# CPU.net
KiCad netlist of a schematic drawn in Altium Designer
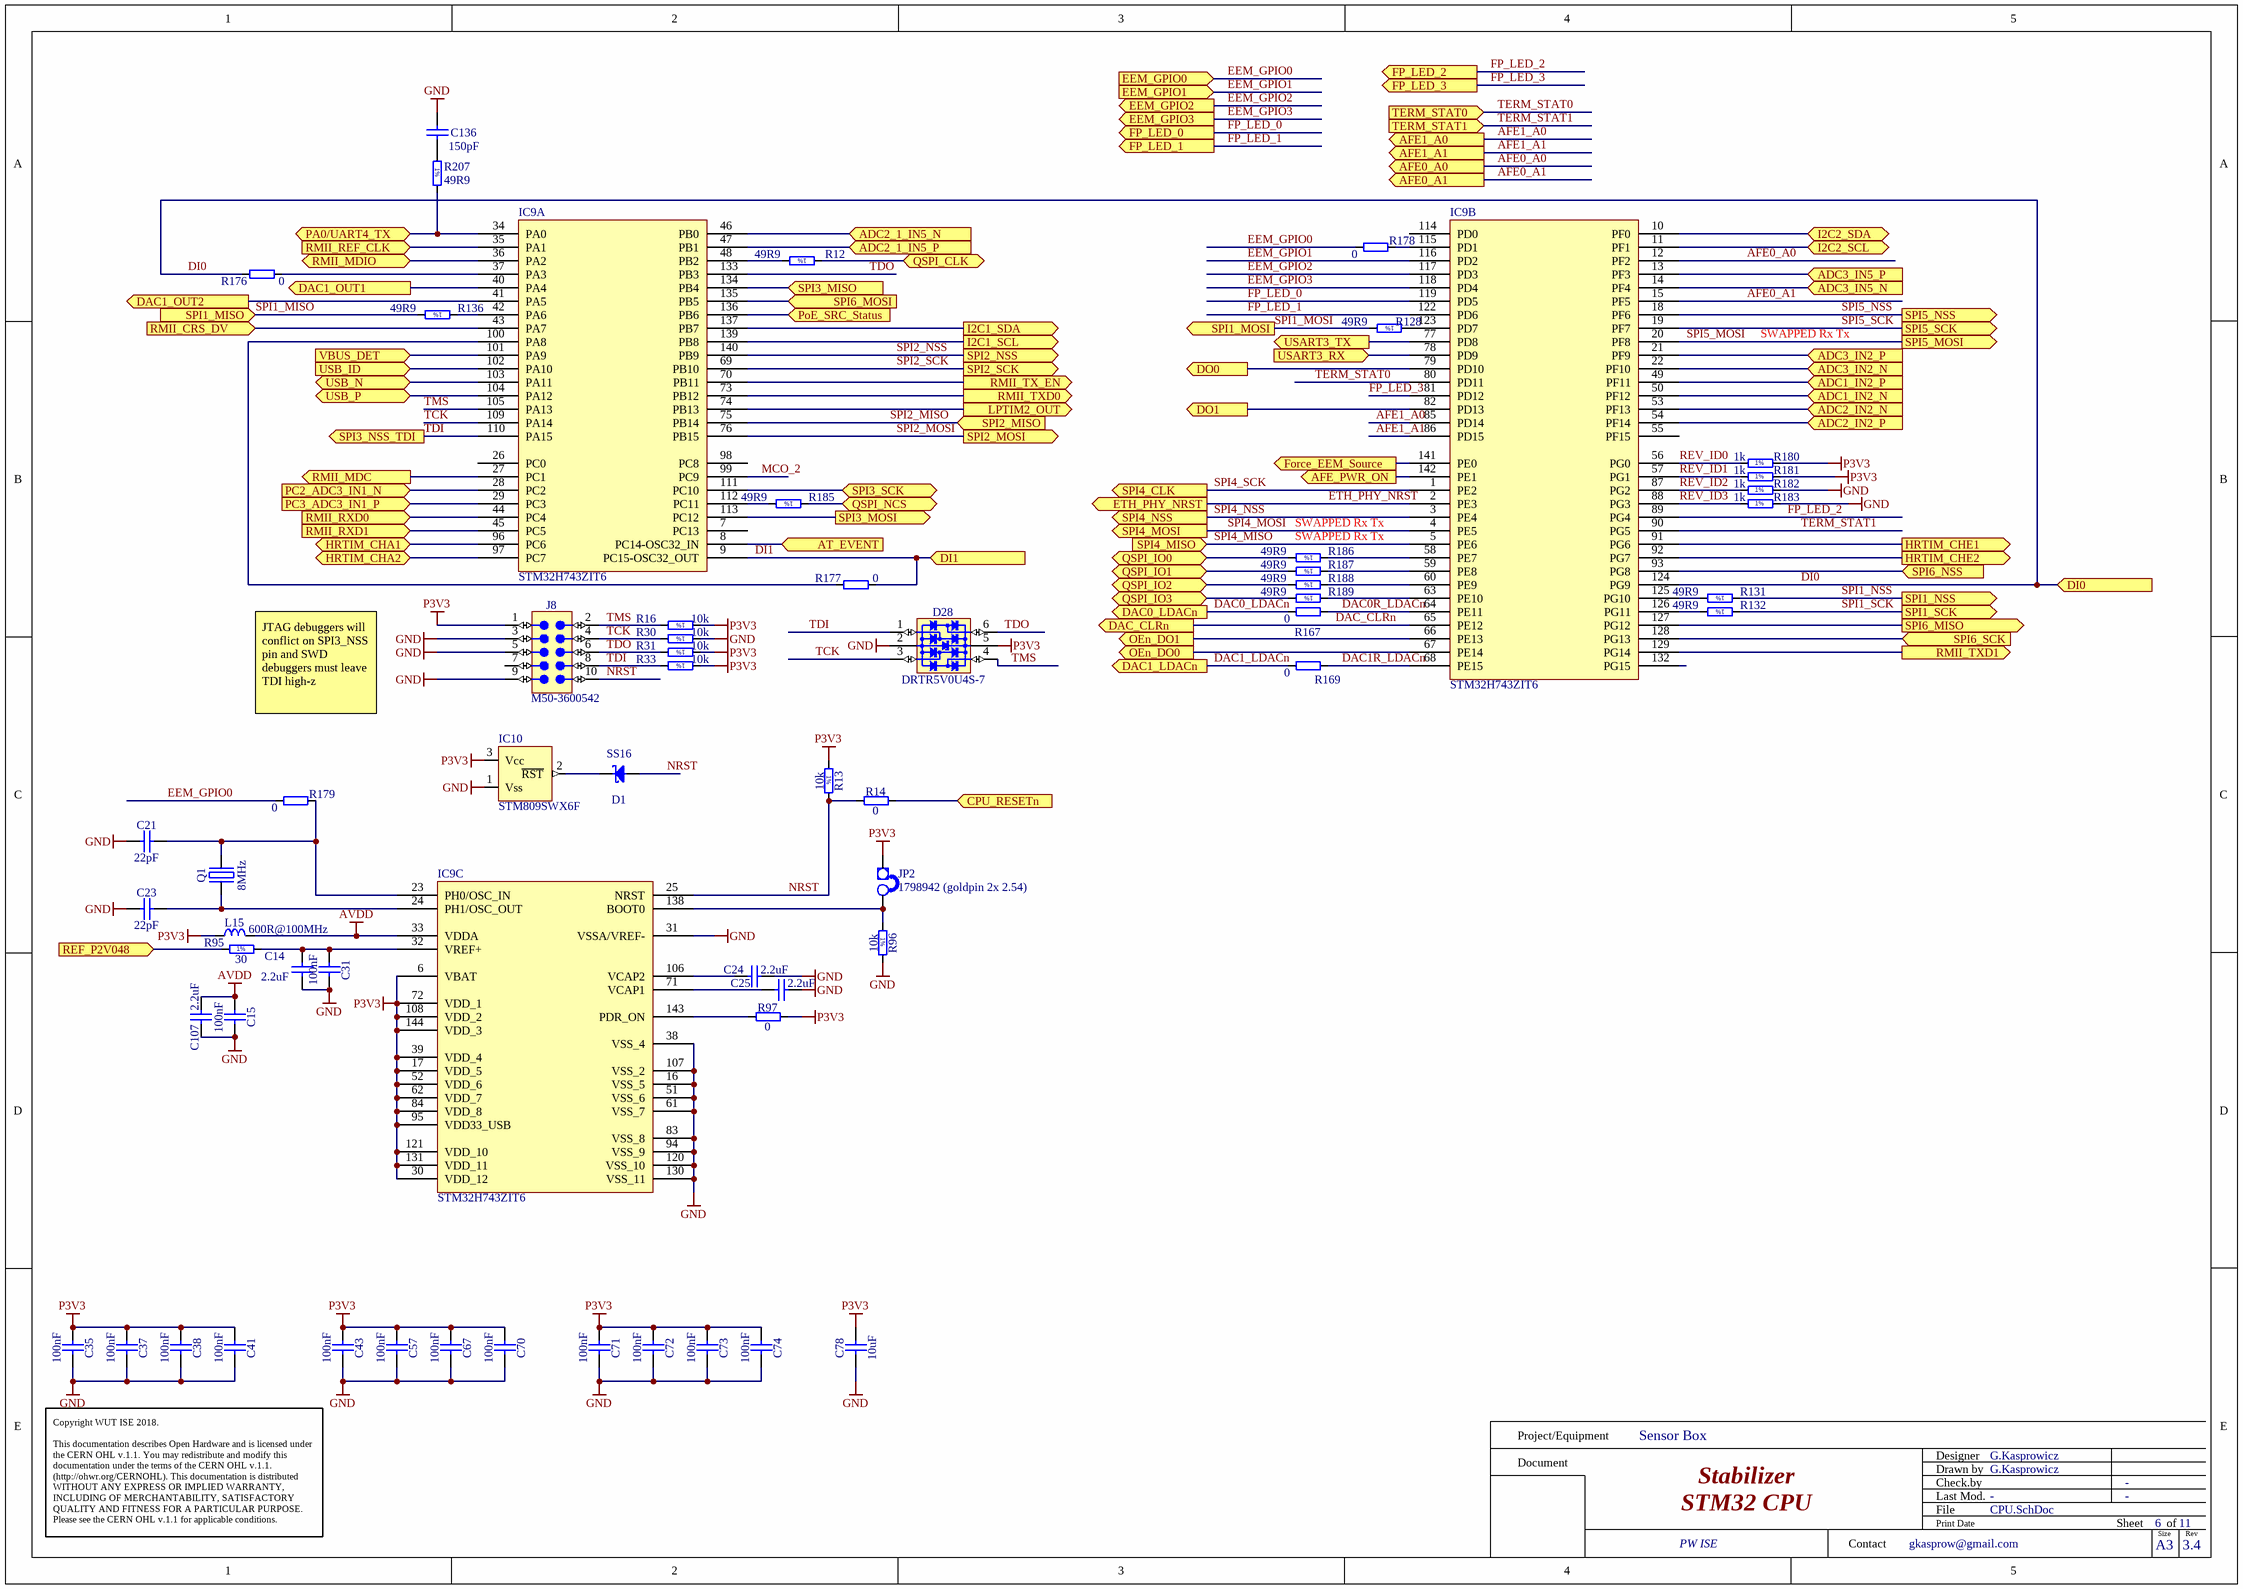
[diagram p0: CPU.SchDoc]

(export (version "E")
  (design (tool "Eeschema 10.0.6"))
  (components
    (comp (ref "C14")
      (value "2.2uF")
      (footprint "CAPC1608X90N")
      (description "Non-polarised capacitor")
      (fields
        (field (name "PART NUMBER") "CC0603_2.2UF_10V_20%_X7R")
        (field (name "VOLTAGE") "10V")
        (field (name "AUTHOR") "CERN DEM JLC")
      )
      (libsource (lib "Capacitors") (part "Capacitor - non polarized"))
    )
    (comp (ref "C15")
      (value "100nF")
      (footprint "CAPC1005X55N")
      (description "Non-polarised capacitor")
      (fields
        (field (name "PART NUMBER") "CC0402_100NF_16V_10%_X5R")
        (field (name "VOLTAGE") "16V")
        (field (name "AUTHOR") "CERN DEM JLC")
      )
      (libsource (lib "Capacitors") (part "Capacitor - non polarized"))
    )
    (comp (ref "C21")
      (value "22pF")
      (footprint "CAPC1005X55N")
      (description "Non-polarised capacitor")
      (fields
        (field (name "PART NUMBER") "CC0402_22PF_50V_5%_C0G")
        (field (name "VOLTAGE") "50V")
        (field (name "AUTHOR") "CERN DEM JLC")
      )
      (libsource (lib "Capacitors") (part "Capacitor - non polarized"))
    )
    (comp (ref "C23")
      (value "22pF")
      (footprint "CAPC1005X55N")
      (description "Non-polarised capacitor")
      (fields
        (field (name "PART NUMBER") "CC0402_22PF_50V_5%_C0G")
        (field (name "VOLTAGE") "50V")
        (field (name "AUTHOR") "CERN DEM JLC")
      )
      (libsource (lib "Capacitors") (part "Capacitor - non polarized"))
    )
    (comp (ref "C24")
      (value "2.2uF")
      (footprint "CAPC1608X90N")
      (description "Non-polarised capacitor")
      (fields
        (field (name "PART NUMBER") "CC0603_2.2UF_10V_20%_X7R")
        (field (name "VOLTAGE") "10V")
        (field (name "AUTHOR") "CERN DEM JLC")
      )
      (libsource (lib "Capacitors") (part "Capacitor - non polarized"))
    )
    (comp (ref "C25")
      (value "2.2uF")
      (footprint "CAPC1608X90N")
      (description "Non-polarised capacitor")
      (fields
        (field (name "PART NUMBER") "CC0603_2.2UF_10V_20%_X7R")
        (field (name "VOLTAGE") "10V")
        (field (name "AUTHOR") "CERN DEM JLC")
      )
      (libsource (lib "Capacitors") (part "Capacitor - non polarized"))
    )
    (comp (ref "C31")
      (value "100nF")
      (footprint "CAPC1005X55N")
      (description "Non-polarised capacitor")
      (fields
        (field (name "PART NUMBER") "CC0402_100NF_16V_10%_X5R")
        (field (name "VOLTAGE") "16V")
        (field (name "AUTHOR") "CERN DEM JLC")
      )
      (libsource (lib "Capacitors") (part "Capacitor - non polarized"))
    )
    (comp (ref "C35")
      (value "100nF")
      (footprint "CAPC1005X55N")
      (description "Non-polarised capacitor")
      (fields
        (field (name "PART NUMBER") "CC0402_100NF_16V_10%_X5R")
        (field (name "VOLTAGE") "16V")
        (field (name "AUTHOR") "CERN DEM JLC")
      )
      (libsource (lib "Capacitors") (part "Capacitor - non polarized"))
    )
    (comp (ref "C37")
      (value "100nF")
      (footprint "CAPC1005X55N")
      (description "Non-polarised capacitor")
      (fields
        (field (name "PART NUMBER") "CC0402_100NF_16V_10%_X5R")
        (field (name "VOLTAGE") "16V")
        (field (name "AUTHOR") "CERN DEM JLC")
      )
      (libsource (lib "Capacitors") (part "Capacitor - non polarized"))
    )
    (comp (ref "C38")
      (value "100nF")
      (footprint "CAPC1005X55N")
      (description "Non-polarised capacitor")
      (fields
        (field (name "PART NUMBER") "CC0402_100NF_16V_10%_X5R")
        (field (name "VOLTAGE") "16V")
        (field (name "AUTHOR") "CERN DEM JLC")
      )
      (libsource (lib "Capacitors") (part "Capacitor - non polarized"))
    )
    (comp (ref "C41")
      (value "100nF")
      (footprint "CAPC1005X55N")
      (description "Non-polarised capacitor")
      (fields
        (field (name "PART NUMBER") "CC0402_100NF_16V_10%_X5R")
        (field (name "VOLTAGE") "16V")
        (field (name "AUTHOR") "CERN DEM JLC")
      )
      (libsource (lib "Capacitors") (part "Capacitor - non polarized"))
    )
    (comp (ref "C43")
      (value "100nF")
      (footprint "CAPC1005X55N")
      (description "Non-polarised capacitor")
      (fields
        (field (name "PART NUMBER") "CC0402_100NF_16V_10%_X5R")
        (field (name "VOLTAGE") "16V")
        (field (name "AUTHOR") "CERN DEM JLC")
      )
      (libsource (lib "Capacitors") (part "Capacitor - non polarized"))
    )
    (comp (ref "C57")
      (value "100nF")
      (footprint "CAPC1005X55N")
      (description "Non-polarised capacitor")
      (fields
        (field (name "PART NUMBER") "CC0402_100NF_16V_10%_X5R")
        (field (name "VOLTAGE") "16V")
        (field (name "AUTHOR") "CERN DEM JLC")
      )
      (libsource (lib "Capacitors") (part "Capacitor - non polarized"))
    )
    (comp (ref "C67")
      (value "100nF")
      (footprint "CAPC1005X55N")
      (description "Non-polarised capacitor")
      (fields
        (field (name "PART NUMBER") "CC0402_100NF_16V_10%_X5R")
        (field (name "VOLTAGE") "16V")
        (field (name "AUTHOR") "CERN DEM JLC")
      )
      (libsource (lib "Capacitors") (part "Capacitor - non polarized"))
    )
    (comp (ref "C70")
      (value "100nF")
      (footprint "CAPC1005X55N")
      (description "Non-polarised capacitor")
      (fields
        (field (name "PART NUMBER") "CC0402_100NF_16V_10%_X5R")
        (field (name "VOLTAGE") "16V")
        (field (name "AUTHOR") "CERN DEM JLC")
      )
      (libsource (lib "Capacitors") (part "Capacitor - non polarized"))
    )
    (comp (ref "C71")
      (value "100nF")
      (footprint "CAPC1005X55N")
      (description "Non-polarised capacitor")
      (fields
        (field (name "PART NUMBER") "CC0402_100NF_16V_10%_X5R")
        (field (name "VOLTAGE") "16V")
        (field (name "AUTHOR") "CERN DEM JLC")
      )
      (libsource (lib "Capacitors") (part "Capacitor - non polarized"))
    )
    (comp (ref "C72")
      (value "100nF")
      (footprint "CAPC1005X55N")
      (description "Non-polarised capacitor")
      (fields
        (field (name "PART NUMBER") "CC0402_100NF_16V_10%_X5R")
        (field (name "VOLTAGE") "16V")
        (field (name "AUTHOR") "CERN DEM JLC")
      )
      (libsource (lib "Capacitors") (part "Capacitor - non polarized"))
    )
    (comp (ref "C73")
      (value "100nF")
      (footprint "CAPC1005X55N")
      (description "Non-polarised capacitor")
      (fields
        (field (name "PART NUMBER") "CC0402_100NF_16V_10%_X5R")
        (field (name "VOLTAGE") "16V")
        (field (name "AUTHOR") "CERN DEM JLC")
      )
      (libsource (lib "Capacitors") (part "Capacitor - non polarized"))
    )
    (comp (ref "C74")
      (value "100nF")
      (footprint "CAPC1005X55N")
      (description "Non-polarised capacitor")
      (fields
        (field (name "PART NUMBER") "CC0402_100NF_16V_10%_X5R")
        (field (name "VOLTAGE") "16V")
        (field (name "AUTHOR") "CERN DEM JLC")
      )
      (libsource (lib "Capacitors") (part "Capacitor - non polarized"))
    )
    (comp (ref "C78")
      (value "10uF")
      (footprint "CAPC2012X95N")
      (description "Non-polarised capacitor")
      (fields
        (field (name "PART NUMBER") "CC0805_10UF_25V_10%_X5R")
        (field (name "VOLTAGE") "25V")
        (field (name "AUTHOR") "CERN DEM JLC")
      )
      (libsource (lib "Capacitors") (part "Capacitor - non polarized"))
    )
    (comp (ref "C107")
      (value "2.2uF")
      (footprint "CAPC1608X90N")
      (description "Non-polarised capacitor")
      (fields
        (field (name "PART NUMBER") "CC0603_2.2UF_10V_20%_X7R")
        (field (name "VOLTAGE") "10V")
        (field (name "AUTHOR") "CERN DEM JLC")
      )
      (libsource (lib "Capacitors") (part "Capacitor - non polarized"))
    )
    (comp (ref "C136")
      (value "150pF")
      (footprint "CAPC1608X87N")
      (description "Non-polarised capacitor")
      (fields
        (field (name "PART NUMBER") "CC0603_150PF_50V_1%_NP0")
        (field (name "VOLTAGE") "50V")
        (field (name "AUTHOR") "CERN DEM MR")
      )
      (libsource (lib "Capacitors") (part "Capacitor - non polarized"))
    )
    (comp (ref "D1")
      (value "SS16")
      (footprint "DIOM5127X229N")
      (description "Schottky Diode")
      (fields
        (field (name "VOLTAGE") "60V")
        (field (name "POWER") "1A")
        (field (name "AUTHOR") "CERN DEM JLC")
      )
      (libsource (lib "ICs And Semiconductors") (part "Diode Schottky"))
    )
    (comp (ref "D28")
      (value "DRTR5V0U4S-7")
      (footprint "SOT65P210X110-6N")
      (description "Integrated Quad Ultra-Low Capacitance ESD Protection")
      (fields (field (name "MANUFACTURER") "DIODES") (field (name "AUTHOR") "GK"))
      (libsource (lib "Diodes") (part "D_TVS_DRTR5V0U4S-7"))
    )
    (comp (ref "IC9")
      (value "STM32H743ZIT6")
      (footprint "TSQFP50P2200X2200X160-144N")
      (description "32-bit Arm® Cortex-M7 400MHz MCUs, up to 2MB Flash,\r\n1MB RAM, 46 com. and analog interfaces")
      (libsource (lib "LIBRARY_SCH") (part "UPC_STM32H743ZIT6"))
    )
    (comp (ref "IC10")
      (value "STM809SWX6F")
      (footprint "SOT-23")
      (description "2.93V  Reset circuit")
      (libsource (lib "LIBRARY_SCH") (part "VMON_STM809"))
    )
    (comp (ref "J8")
      (value "Header 10")
      (footprint "HARWIN_M50-3600542")
      (description "10 Contacts - Pitch 1.27mm - Dual Row SMT Vertical Pin Header (Post Lead = 3mm, Insulator 1mm)")
      (fields
        (field (name "PART NUMBER") "HARWIN_M50-3600542")
        (field (name "MANUFACTURER") "HARWIN")
        (field (name "MANUFACTURER PART NUMBER") "M50-3600542")
        (field (name "AUTHOR") "GK")
      )
      (libsource (lib "Connectors") (part "CON_2x10 1.27 SMT_male_HARWIN"))
    )
    (comp (ref "JP2")
      (value "1798942 (goldpin 2x 2.54)")
      (footprint "jump")
      (description "Jumper")
      (libsource (lib "LIBRARY_SCH") (part "JUMPER"))
    )
    (comp (ref "L15")
      (value "600R@100MHz")
      (footprint "INDC1005X55N")
      (description "Inductor")
      (fields
        (field (name "PART NUMBER") "IND0402_MURATA_BLM15HD601SN1")
        (field (name "POWER") "300mA")
        (field (name "AUTHOR") "CERN DEM JLC")
      )
      (libsource (lib "Inductors & Transformers") (part "Inductor"))
    )
    (comp (ref "Q1")
      (value "8MHz")
      (footprint "XTAL_TXC_7A")
      (description "Quartz Crystal")
      (fields
        (field (name "PART NUMBER") "XTAL_8MHZ_TXC_7A-8.000MAAE-T")
        (field (name "MANUFACTURER") "TXC CORPORATION")
        (field (name "AUTHOR") "CERN DEM JLC")
      )
      (libsource (lib "ICs And Semiconductors") (part "Quartz Crystal"))
    )
    (comp (ref "R12")
      (value "49R9")
      (footprint "RESC1005X40N")
      (description "Resistor - 1%")
      (fields
        (field (name "PART NUMBER") "R0402_49R9_1%_0.0625W_100PPM")
        (field (name "POWER") "0.0625W")
        (field (name "AUTHOR") "CERN DEM JLC")
      )
      (libsource (lib "Resistors") (part "Resistor - 1%"))
    )
    (comp (ref "R13")
      (value "10k")
      (footprint "RESC1005X40N")
      (description "Resistor - 1%")
      (fields
        (field (name "PART NUMBER") "R0402_10K_1%_0.0625W_100PPM")
        (field (name "POWER") "0.0625W")
        (field (name "AUTHOR") "CERN DEM JLC")
      )
      (libsource (lib "Resistors") (part "Resistor - 1%"))
    )
    (comp (ref "R14")
      (value "0")
      (footprint "RESC1005X40N")
      (description "Resistor")
      (fields
        (field (name "PART NUMBER") "R0402_0R_JUMPER")
        (field (name "MANUFACTURER") "GENERIC")
        (field (name "AUTHOR") "CERN DEM JLC")
      )
      (libsource (lib "Resistors") (part "Resistor"))
    )
    (comp (ref "R16")
      (value "10k")
      (footprint "RESC1005X40N")
      (description "Resistor - 1%")
      (fields
        (field (name "PART NUMBER") "R0402_10K_1%_0.0625W_100PPM")
        (field (name "POWER") "0.0625W")
        (field (name "AUTHOR") "CERN DEM JLC")
      )
      (libsource (lib "Resistors") (part "Resistor - 1%"))
    )
    (comp (ref "R30")
      (value "10k")
      (footprint "RESC1005X40N")
      (description "Resistor - 1%")
      (fields
        (field (name "PART NUMBER") "R0402_10K_1%_0.0625W_100PPM")
        (field (name "POWER") "0.0625W")
        (field (name "AUTHOR") "CERN DEM JLC")
      )
      (libsource (lib "Resistors") (part "Resistor - 1%"))
    )
    (comp (ref "R31")
      (value "10k")
      (footprint "RESC1005X40N")
      (description "Resistor - 1%")
      (fields
        (field (name "PART NUMBER") "R0402_10K_1%_0.0625W_100PPM")
        (field (name "POWER") "0.0625W")
        (field (name "AUTHOR") "CERN DEM JLC")
      )
      (libsource (lib "Resistors") (part "Resistor - 1%"))
    )
    (comp (ref "R33")
      (value "10k")
      (footprint "RESC1005X40N")
      (description "Resistor - 1%")
      (fields
        (field (name "PART NUMBER") "R0402_10K_1%_0.0625W_100PPM")
        (field (name "POWER") "0.0625W")
        (field (name "AUTHOR") "CERN DEM JLC")
      )
      (libsource (lib "Resistors") (part "Resistor - 1%"))
    )
    (comp (ref "R95")
      (value "30")
      (footprint "RESC1608X55N")
      (description "Resistor - 1%")
      (fields
        (field (name "PART NUMBER") "R0603_30R_1%_0.1W_100PPM")
        (field (name "POWER") "0.1W")
        (field (name "AUTHOR") "CERN DEM JLC")
      )
      (libsource (lib "Resistors") (part "Resistor - 1%"))
    )
    (comp (ref "R96")
      (value "10k")
      (footprint "RESC1005X40N")
      (description "Resistor - 1%")
      (fields
        (field (name "PART NUMBER") "R0402_10K_1%_0.0625W_100PPM")
        (field (name "POWER") "0.0625W")
        (field (name "AUTHOR") "CERN DEM JLC")
      )
      (libsource (lib "Resistors") (part "Resistor - 1%"))
    )
    (comp (ref "R97")
      (value "0")
      (footprint "RESC1005X40N")
      (description "Resistor")
      (fields
        (field (name "PART NUMBER") "R0402_0R_JUMPER")
        (field (name "MANUFACTURER") "GENERIC")
        (field (name "AUTHOR") "CERN DEM JLC")
      )
      (libsource (lib "Resistors") (part "Resistor"))
    )
    (comp (ref "R128")
      (value "49R9")
      (footprint "RESC1005X40N")
      (description "Resistor - 1%")
      (fields
        (field (name "PART NUMBER") "R0402_49R9_1%_0.0625W_100PPM")
        (field (name "POWER") "0.0625W")
        (field (name "AUTHOR") "CERN DEM JLC")
      )
      (libsource (lib "Resistors") (part "Resistor - 1%"))
    )
    (comp (ref "R131")
      (value "49R9")
      (footprint "RESC1005X40N")
      (description "Resistor - 1%")
      (fields
        (field (name "PART NUMBER") "R0402_49R9_1%_0.0625W_100PPM")
        (field (name "POWER") "0.0625W")
        (field (name "AUTHOR") "CERN DEM JLC")
      )
      (libsource (lib "Resistors") (part "Resistor - 1%"))
    )
    (comp (ref "R132")
      (value "49R9")
      (footprint "RESC1005X40N")
      (description "Resistor - 1%")
      (fields
        (field (name "PART NUMBER") "R0402_49R9_1%_0.0625W_100PPM")
        (field (name "POWER") "0.0625W")
        (field (name "AUTHOR") "CERN DEM JLC")
      )
      (libsource (lib "Resistors") (part "Resistor - 1%"))
    )
    (comp (ref "R136")
      (value "49R9")
      (footprint "RESC1005X40N")
      (description "Resistor - 1%")
      (fields
        (field (name "PART NUMBER") "R0402_49R9_1%_0.0625W_100PPM")
        (field (name "POWER") "0.0625W")
        (field (name "AUTHOR") "CERN DEM JLC")
      )
      (libsource (lib "Resistors") (part "Resistor - 1%"))
    )
    (comp (ref "R167")
      (value "0")
      (footprint "RESC1608X55N")
      (description "Resistor")
      (fields
        (field (name "PART NUMBER") "R0603_0R_JUMPER")
        (field (name "MANUFACTURER") "GENERIC")
        (field (name "AUTHOR") "CERN DEM JLC")
      )
      (libsource (lib "Resistors") (part "Resistor"))
    )
    (comp (ref "R169")
      (value "0")
      (footprint "RESC1608X55N")
      (description "Resistor")
      (fields
        (field (name "PART NUMBER") "R0603_0R_JUMPER")
        (field (name "MANUFACTURER") "GENERIC")
        (field (name "AUTHOR") "CERN DEM JLC")
      )
      (libsource (lib "Resistors") (part "Resistor"))
    )
    (comp (ref "R176")
      (value "0")
      (footprint "RESC1608X55N")
      (description "Resistor")
      (fields
        (field (name "PART NUMBER") "R0603_0R_JUMPER")
        (field (name "MANUFACTURER") "GENERIC")
        (field (name "AUTHOR") "CERN DEM JLC")
      )
      (libsource (lib "Resistors") (part "Resistor"))
    )
    (comp (ref "R177")
      (value "0")
      (footprint "RESC1608X55N")
      (description "Resistor")
      (fields
        (field (name "PART NUMBER") "R0603_0R_JUMPER")
        (field (name "MANUFACTURER") "GENERIC")
        (field (name "AUTHOR") "CERN DEM JLC")
      )
      (libsource (lib "Resistors") (part "Resistor"))
    )
    (comp (ref "R178")
      (value "0")
      (footprint "RESC1608X55N")
      (description "Resistor")
      (fields
        (field (name "PART NUMBER") "R0603_0R_JUMPER")
        (field (name "MANUFACTURER") "GENERIC")
        (field (name "AUTHOR") "CERN DEM JLC")
      )
      (libsource (lib "Resistors") (part "Resistor"))
    )
    (comp (ref "R179")
      (value "0")
      (footprint "RESC1608X55N")
      (description "Resistor")
      (fields
        (field (name "PART NUMBER") "R0603_0R_JUMPER")
        (field (name "MANUFACTURER") "GENERIC")
        (field (name "AUTHOR") "CERN DEM JLC")
      )
      (libsource (lib "Resistors") (part "Resistor"))
    )
    (comp (ref "R180")
      (value "1k")
      (footprint "RESC1608X55N")
      (description "Resistor - 1%")
      (fields
        (field (name "PART NUMBER") "R0603_1K_1%_0.1W_100PPM")
        (field (name "POWER") "0.1W")
        (field (name "AUTHOR") "CERN DEM JLC")
      )
      (libsource (lib "Resistors") (part "Resistor - 1%"))
    )
    (comp (ref "R181")
      (value "1k")
      (footprint "RESC1608X55N")
      (description "Resistor - 1%")
      (fields
        (field (name "PART NUMBER") "R0603_1K_1%_0.1W_100PPM")
        (field (name "POWER") "0.1W")
        (field (name "AUTHOR") "CERN DEM JLC")
      )
      (libsource (lib "Resistors") (part "Resistor - 1%"))
    )
    (comp (ref "R182")
      (value "1k")
      (footprint "RESC1608X55N")
      (description "Resistor - 1%")
      (fields
        (field (name "PART NUMBER") "R0603_1K_1%_0.1W_100PPM")
        (field (name "POWER") "0.1W")
        (field (name "AUTHOR") "CERN DEM JLC")
      )
      (libsource (lib "Resistors") (part "Resistor - 1%"))
    )
    (comp (ref "R183")
      (value "1k")
      (footprint "RESC1608X55N")
      (description "Resistor - 1%")
      (fields
        (field (name "PART NUMBER") "R0603_1K_1%_0.1W_100PPM")
        (field (name "POWER") "0.1W")
        (field (name "AUTHOR") "CERN DEM JLC")
      )
      (libsource (lib "Resistors") (part "Resistor - 1%"))
    )
    (comp (ref "R185")
      (value "49R9")
      (footprint "RESC1005X40N")
      (description "Resistor - 1%")
      (fields
        (field (name "PART NUMBER") "R0402_49R9_1%_0.0625W_100PPM")
        (field (name "POWER") "0.0625W")
        (field (name "AUTHOR") "CERN DEM JLC")
      )
      (libsource (lib "Resistors") (part "Resistor - 1%"))
    )
    (comp (ref "R186")
      (value "49R9")
      (footprint "RESC1005X40N")
      (description "Resistor - 1%")
      (fields
        (field (name "PART NUMBER") "R0402_49R9_1%_0.0625W_100PPM")
        (field (name "POWER") "0.0625W")
        (field (name "AUTHOR") "CERN DEM JLC")
      )
      (libsource (lib "Resistors") (part "Resistor - 1%"))
    )
    (comp (ref "R187")
      (value "49R9")
      (footprint "RESC1005X40N")
      (description "Resistor - 1%")
      (fields
        (field (name "PART NUMBER") "R0402_49R9_1%_0.0625W_100PPM")
        (field (name "POWER") "0.0625W")
        (field (name "AUTHOR") "CERN DEM JLC")
      )
      (libsource (lib "Resistors") (part "Resistor - 1%"))
    )
    (comp (ref "R188")
      (value "49R9")
      (footprint "RESC1005X40N")
      (description "Resistor - 1%")
      (fields
        (field (name "PART NUMBER") "R0402_49R9_1%_0.0625W_100PPM")
        (field (name "POWER") "0.0625W")
        (field (name "AUTHOR") "CERN DEM JLC")
      )
      (libsource (lib "Resistors") (part "Resistor - 1%"))
    )
    (comp (ref "R189")
      (value "49R9")
      (footprint "RESC1005X40N")
      (description "Resistor - 1%")
      (fields
        (field (name "PART NUMBER") "R0402_49R9_1%_0.0625W_100PPM")
        (field (name "POWER") "0.0625W")
        (field (name "AUTHOR") "CERN DEM JLC")
      )
      (libsource (lib "Resistors") (part "Resistor - 1%"))
    )
    (comp (ref "R207")
      (value "49R9")
      (footprint "RESC1005X40N")
      (description "Resistor - 1%")
      (fields
        (field (name "PART NUMBER") "R0402_49R9_1%_0.0625W_100PPM")
        (field (name "POWER") "0.0625W")
        (field (name "AUTHOR") "CERN DEM JLC")
      )
      (libsource (lib "Resistors") (part "Resistor - 1%"))
    )
  )
  (nets
    (net (code "1") (name "/ADC1_IN2_N") (class "Default")
      (node (ref "IC9") (pin "50") (pinfunction "PF12_50") (pintype "passive"))
    )
    (net (code "2") (name "/ADC1_IN2_P") (class "Default")
      (node (ref "IC9") (pin "49") (pinfunction "PF11_49") (pintype "passive"))
    )
    (net (code "3") (name "/ADC2_1_IN5_N") (class "Default")
      (node (ref "IC9") (pin "46") (pinfunction "PB0_46") (pintype "passive"))
    )
    (net (code "4") (name "/ADC2_1_IN5_P") (class "Default")
      (node (ref "IC9") (pin "47") (pinfunction "PB1_47") (pintype "passive"))
    )
    (net (code "5") (name "/ADC2_IN2_N") (class "Default")
      (node (ref "IC9") (pin "53") (pinfunction "PF13_53") (pintype "passive"))
    )
    (net (code "6") (name "/ADC2_IN2_P") (class "Default")
      (node (ref "IC9") (pin "54") (pinfunction "PF14_54") (pintype "passive"))
    )
    (net (code "7") (name "/ADC3_IN2_N") (class "Default")
      (node (ref "IC9") (pin "22") (pinfunction "PF10_22") (pintype "passive"))
    )
    (net (code "8") (name "/ADC3_IN2_P") (class "Default")
      (node (ref "IC9") (pin "21") (pinfunction "PF9_21") (pintype "passive"))
    )
    (net (code "9") (name "/ADC3_IN5_N") (class "Default")
      (node (ref "IC9") (pin "14") (pinfunction "PF4_14") (pintype "passive"))
    )
    (net (code "10") (name "/ADC3_IN5_P") (class "Default")
      (node (ref "IC9") (pin "13") (pinfunction "PF3_13") (pintype "passive"))
    )
    (net (code "11") (name "/AFE0_A0") (class "Default")
      (node (ref "IC9") (pin "12") (pinfunction "PF2_12") (pintype "passive"))
    )
    (net (code "12") (name "/AFE0_A1") (class "Default")
      (node (ref "IC9") (pin "15") (pinfunction "PF5_15") (pintype "passive"))
    )
    (net (code "13") (name "/AFE1_A0") (class "Default")
      (node (ref "IC9") (pin "85") (pinfunction "PD14_85") (pintype "passive"))
    )
    (net (code "14") (name "/AFE1_A1") (class "Default")
      (node (ref "IC9") (pin "86") (pinfunction "PD15_86") (pintype "passive"))
    )
    (net (code "15") (name "/AFE_PWR_ON") (class "Default")
      (node (ref "IC9") (pin "142") (pinfunction "PE1_142") (pintype "passive"))
    )
    (net (code "16") (name "/AT_EVENT") (class "Default")
      (node (ref "IC9") (pin "8") (pinfunction "PC14-OSC32_IN_8") (pintype "passive"))
    )
    (net (code "17") (name "/CPU_RESETn") (class "Default")
      (node (ref "R14") (pin "2") (pinfunction "2_2") (pintype "passive"))
    )
    (net (code "18") (name "/DAC0R_LDACn") (class "Default")
      (node (ref "IC9") (pin "64") (pinfunction "PE11_64") (pintype "passive"))
      (node (ref "R167") (pin "2") (pinfunction "2_2") (pintype "passive"))
    )
    (net (code "19") (name "/DAC0_LDACn") (class "Default")
      (node (ref "R167") (pin "1") (pinfunction "1_1") (pintype "passive"))
    )
    (net (code "20") (name "/DAC1R_LDACn") (class "Default")
      (node (ref "IC9") (pin "68") (pinfunction "PE15_68") (pintype "passive"))
      (node (ref "R169") (pin "2") (pinfunction "2_2") (pintype "passive"))
    )
    (net (code "21") (name "/DAC1_LDACn") (class "Default")
      (node (ref "R169") (pin "1") (pinfunction "1_1") (pintype "passive"))
    )
    (net (code "22") (name "/DAC1_OUT1") (class "Default")
      (node (ref "IC9") (pin "40") (pinfunction "PA4_40") (pintype "passive"))
    )
    (net (code "23") (name "/DAC1_OUT2") (class "Default")
      (node (ref "IC9") (pin "41") (pinfunction "PA5_41") (pintype "passive"))
    )
    (net (code "24") (name "/DAC_CLRn") (class "Default")
      (node (ref "IC9") (pin "65") (pinfunction "PE12_65") (pintype "passive"))
    )
    (net (code "25") (name "/DI0") (class "Default")
      (node (ref "IC9") (pin "124") (pinfunction "PG9_124") (pintype "passive"))
      (node (ref "R176") (pin "2") (pinfunction "2_2") (pintype "passive"))
    )
    (net (code "26") (name "/DI1") (class "Default")
      (node (ref "IC9") (pin "9") (pinfunction "PC15-OSC32_OUT_9") (pintype "passive"))
      (node (ref "R177") (pin "1") (pinfunction "1_1") (pintype "passive"))
    )
    (net (code "27") (name "/DO0") (class "Default")
      (node (ref "IC9") (pin "79") (pinfunction "PD10_79") (pintype "passive"))
    )
    (net (code "28") (name "/DO1") (class "Default")
      (node (ref "IC9") (pin "82") (pinfunction "PD13_82") (pintype "passive"))
    )
    (net (code "29") (name "/EEM_GPIO0") (class "Default")
      (node (ref "R178") (pin "1") (pinfunction "1_1") (pintype "passive"))
      (node (ref "R179") (pin "1") (pinfunction "1_1") (pintype "passive"))
    )
    (net (code "30") (name "/EEM_GPIO1") (class "Default")
      (node (ref "IC9") (pin "116") (pinfunction "PD2_116") (pintype "passive"))
    )
    (net (code "31") (name "/EEM_GPIO2") (class "Default")
      (node (ref "IC9") (pin "117") (pinfunction "PD3_117") (pintype "passive"))
    )
    (net (code "32") (name "/EEM_GPIO3") (class "Default")
      (node (ref "IC9") (pin "118") (pinfunction "PD4_118") (pintype "passive"))
    )
    (net (code "33") (name "/ETH_PHY_NRST") (class "Default")
      (node (ref "IC9") (pin "2") (pinfunction "PE3_2") (pintype "passive"))
    )
    (net (code "34") (name "/FP_LED_0") (class "Default")
      (node (ref "IC9") (pin "119") (pinfunction "PD5_119") (pintype "passive"))
    )
    (net (code "35") (name "/FP_LED_1") (class "Default")
      (node (ref "IC9") (pin "122") (pinfunction "PD6_122") (pintype "passive"))
    )
    (net (code "36") (name "/FP_LED_2") (class "Default")
      (node (ref "IC9") (pin "89") (pinfunction "PG4_89") (pintype "passive"))
    )
    (net (code "37") (name "/FP_LED_3") (class "Default")
      (node (ref "IC9") (pin "81") (pinfunction "PD12_81") (pintype "passive"))
    )
    (net (code "38") (name "/Force_EEM_Source") (class "Default")
      (node (ref "IC9") (pin "141") (pinfunction "PE0_141") (pintype "passive"))
    )
    (net (code "39") (name "/HRTIM_CHA1") (class "Default")
      (node (ref "IC9") (pin "96") (pinfunction "PC6_96") (pintype "passive"))
    )
    (net (code "40") (name "/HRTIM_CHA2") (class "Default")
      (node (ref "IC9") (pin "97") (pinfunction "PC7_97") (pintype "passive"))
    )
    (net (code "41") (name "/HRTIM_CHE1") (class "Default")
      (node (ref "IC9") (pin "91") (pinfunction "PG6_91") (pintype "passive"))
    )
    (net (code "42") (name "/HRTIM_CHE2") (class "Default")
      (node (ref "IC9") (pin "92") (pinfunction "PG7_92") (pintype "passive"))
    )
    (net (code "43") (name "/I2C1_SCL") (class "Default")
      (node (ref "IC9") (pin "139") (pinfunction "PB8_139") (pintype "passive"))
    )
    (net (code "44") (name "/I2C1_SDA") (class "Default")
      (node (ref "IC9") (pin "137") (pinfunction "PB7_137") (pintype "passive"))
    )
    (net (code "45") (name "/I2C2_SCL") (class "Default")
      (node (ref "IC9") (pin "11") (pinfunction "PF1_11") (pintype "passive"))
    )
    (net (code "46") (name "/I2C2_SDA") (class "Default")
      (node (ref "IC9") (pin "10") (pinfunction "PF0_10") (pintype "passive"))
    )
    (net (code "47") (name "/LPTIM2_OUT") (class "Default")
      (node (ref "IC9") (pin "74") (pinfunction "PB13_74") (pintype "passive"))
    )
    (net (code "48") (name "/MCO_2") (class "Default")
      (node (ref "IC9") (pin "99") (pinfunction "PC9_99") (pintype "passive"))
    )
    (net (code "49") (name "/NRST") (class "Default")
      (node (ref "D1") (pin "2") (pinfunction "A_2") (pintype "passive"))
      (node (ref "IC9") (pin "25") (pinfunction "NRST_25") (pintype "passive"))
      (node (ref "J8") (pin "10") (pinfunction "10_10") (pintype "bidirectional"))
      (node (ref "R13") (pin "2") (pinfunction "2_2") (pintype "passive"))
      (node (ref "R14") (pin "1") (pinfunction "1_1") (pintype "passive"))
    )
    (net (code "50") (name "/OEn_DO0") (class "Default")
      (node (ref "IC9") (pin "67") (pinfunction "PE14_67") (pintype "passive"))
    )
    (net (code "51") (name "/OEn_DO1") (class "Default")
      (node (ref "IC9") (pin "66") (pinfunction "PE13_66") (pintype "passive"))
    )
    (net (code "52") (name "/PA0{slash}UART4_TX") (class "Default")
      (node (ref "IC9") (pin "34") (pinfunction "PA0_34") (pintype "passive"))
      (node (ref "R207") (pin "2") (pinfunction "2_2") (pintype "passive"))
    )
    (net (code "53") (name "/PC2_ADC3_IN1_N") (class "Default")
      (node (ref "IC9") (pin "28") (pinfunction "PC2_28") (pintype "passive"))
    )
    (net (code "54") (name "/PC3_ADC3_IN1_P") (class "Default")
      (node (ref "IC9") (pin "29") (pinfunction "PC3_29") (pintype "passive"))
    )
    (net (code "55") (name "/PoE_SRC_Status") (class "Default")
      (node (ref "IC9") (pin "136") (pinfunction "PB6_136") (pintype "passive"))
    )
    (net (code "56") (name "/QSPI_CLK") (class "Default")
      (node (ref "R12") (pin "1") (pinfunction "1_1") (pintype "passive"))
    )
    (net (code "57") (name "/QSPI_IO0") (class "Default")
      (node (ref "R186") (pin "2") (pinfunction "2_2") (pintype "passive"))
    )
    (net (code "58") (name "/QSPI_IO1") (class "Default")
      (node (ref "R187") (pin "2") (pinfunction "2_2") (pintype "passive"))
    )
    (net (code "59") (name "/QSPI_IO2") (class "Default")
      (node (ref "R188") (pin "2") (pinfunction "2_2") (pintype "passive"))
    )
    (net (code "60") (name "/QSPI_IO3") (class "Default")
      (node (ref "R189") (pin "2") (pinfunction "2_2") (pintype "passive"))
    )
    (net (code "61") (name "/QSPI_NCS") (class "Default")
      (node (ref "R185") (pin "1") (pinfunction "1_1") (pintype "passive"))
    )
    (net (code "62") (name "/REF_P2V048") (class "Default")
      (node (ref "R95") (pin "1") (pinfunction "1_1") (pintype "passive"))
    )
    (net (code "63") (name "/REV_ID0") (class "Default")
      (node (ref "IC9") (pin "56") (pinfunction "PG0_56") (pintype "passive"))
      (node (ref "R180") (pin "1") (pinfunction "1_1") (pintype "passive"))
    )
    (net (code "64") (name "/REV_ID1") (class "Default")
      (node (ref "IC9") (pin "57") (pinfunction "PG1_57") (pintype "passive"))
      (node (ref "R181") (pin "1") (pinfunction "1_1") (pintype "passive"))
    )
    (net (code "65") (name "/REV_ID2") (class "Default")
      (node (ref "IC9") (pin "87") (pinfunction "PG2_87") (pintype "passive"))
      (node (ref "R182") (pin "1") (pinfunction "1_1") (pintype "passive"))
    )
    (net (code "66") (name "/REV_ID3") (class "Default")
      (node (ref "IC9") (pin "88") (pinfunction "PG3_88") (pintype "passive"))
      (node (ref "R183") (pin "1") (pinfunction "1_1") (pintype "passive"))
    )
    (net (code "67") (name "/RMII_CRS_DV") (class "Default")
      (node (ref "IC9") (pin "43") (pinfunction "PA7_43") (pintype "passive"))
    )
    (net (code "68") (name "/RMII_MDC") (class "Default")
      (node (ref "IC9") (pin "27") (pinfunction "PC1_27") (pintype "passive"))
    )
    (net (code "69") (name "/RMII_MDIO") (class "Default")
      (node (ref "IC9") (pin "36") (pinfunction "PA2_36") (pintype "passive"))
    )
    (net (code "70") (name "/RMII_REF_CLK") (class "Default")
      (node (ref "IC9") (pin "35") (pinfunction "PA1_35") (pintype "passive"))
    )
    (net (code "71") (name "/RMII_RXD0") (class "Default")
      (node (ref "IC9") (pin "44") (pinfunction "PC4_44") (pintype "passive"))
    )
    (net (code "72") (name "/RMII_RXD1") (class "Default")
      (node (ref "IC9") (pin "45") (pinfunction "PC5_45") (pintype "passive"))
    )
    (net (code "73") (name "/RMII_TXD0") (class "Default")
      (node (ref "IC9") (pin "73") (pinfunction "PB12_73") (pintype "passive"))
    )
    (net (code "74") (name "/RMII_TXD1") (class "Default")
      (node (ref "IC9") (pin "129") (pinfunction "PG14_129") (pintype "passive"))
    )
    (net (code "75") (name "/RMII_TX_EN") (class "Default")
      (node (ref "IC9") (pin "70") (pinfunction "PB11_70") (pintype "passive"))
    )
    (net (code "76") (name "/SPI1_MISO") (class "Default")
      (node (ref "R136") (pin "2") (pinfunction "2_2") (pintype "passive"))
    )
    (net (code "77") (name "/SPI1_MOSI") (class "Default")
      (node (ref "R128") (pin "2") (pinfunction "2_2") (pintype "passive"))
    )
    (net (code "78") (name "/SPI1_NSS") (class "Default")
      (node (ref "R131") (pin "1") (pinfunction "1_1") (pintype "passive"))
    )
    (net (code "79") (name "/SPI1_SCK") (class "Default")
      (node (ref "R132") (pin "1") (pinfunction "1_1") (pintype "passive"))
    )
    (net (code "80") (name "/SPI2_MISO") (class "Default")
      (node (ref "IC9") (pin "75") (pinfunction "PB14_75") (pintype "passive"))
    )
    (net (code "81") (name "/SPI2_MOSI") (class "Default")
      (node (ref "IC9") (pin "76") (pinfunction "PB15_76") (pintype "passive"))
    )
    (net (code "82") (name "/SPI2_NSS") (class "Default")
      (node (ref "IC9") (pin "140") (pinfunction "PB9_140") (pintype "passive"))
    )
    (net (code "83") (name "/SPI2_SCK") (class "Default")
      (node (ref "IC9") (pin "69") (pinfunction "PB10_69") (pintype "passive"))
    )
    (net (code "84") (name "/SPI3_MISO") (class "Default")
      (node (ref "IC9") (pin "134") (pinfunction "PB4_134") (pintype "passive"))
    )
    (net (code "85") (name "/SPI3_MOSI") (class "Default")
      (node (ref "IC9") (pin "113") (pinfunction "PC12_113") (pintype "passive"))
    )
    (net (code "86") (name "/SPI3_SCK") (class "Default")
      (node (ref "IC9") (pin "111") (pinfunction "PC10_111") (pintype "passive"))
    )
    (net (code "87") (name "/SPI4_MISO") (class "Default")
      (node (ref "IC9") (pin "5") (pinfunction "PE6_5") (pintype "passive"))
    )
    (net (code "88") (name "/SPI4_MOSI") (class "Default")
      (node (ref "IC9") (pin "4") (pinfunction "PE5_4") (pintype "passive"))
    )
    (net (code "89") (name "/SPI4_NSS") (class "Default")
      (node (ref "IC9") (pin "3") (pinfunction "PE4_3") (pintype "passive"))
    )
    (net (code "90") (name "/SPI4_SCK") (class "Default")
      (node (ref "IC9") (pin "1") (pinfunction "PE2_1") (pintype "passive"))
    )
    (net (code "91") (name "/SPI5_MOSI") (class "Default")
      (node (ref "IC9") (pin "20") (pinfunction "PF8_20") (pintype "passive"))
    )
    (net (code "92") (name "/SPI5_NSS") (class "Default")
      (node (ref "IC9") (pin "18") (pinfunction "PF6_18") (pintype "passive"))
    )
    (net (code "93") (name "/SPI5_SCK") (class "Default")
      (node (ref "IC9") (pin "19") (pinfunction "PF7_19") (pintype "passive"))
    )
    (net (code "94") (name "/SPI6_MISO") (class "Default")
      (node (ref "IC9") (pin "127") (pinfunction "PG12_127") (pintype "passive"))
    )
    (net (code "95") (name "/SPI6_MOSI") (class "Default")
      (node (ref "IC9") (pin "135") (pinfunction "PB5_135") (pintype "passive"))
    )
    (net (code "96") (name "/SPI6_NSS") (class "Default")
      (node (ref "IC9") (pin "93") (pinfunction "PG8_93") (pintype "passive"))
    )
    (net (code "97") (name "/SPI6_SCK") (class "Default")
      (node (ref "IC9") (pin "128") (pinfunction "PG13_128") (pintype "passive"))
    )
    (net (code "98") (name "/TCK") (class "Default")
      (node (ref "D28") (pin "3") (pinfunction "I/O2_3") (pintype "bidirectional"))
      (node (ref "IC9") (pin "109") (pinfunction "PA14_109") (pintype "passive"))
      (node (ref "J8") (pin "4") (pinfunction "4_4") (pintype "bidirectional"))
      (node (ref "R30") (pin "2") (pinfunction "2_2") (pintype "passive"))
    )
    (net (code "99") (name "/TDI") (class "Default")
      (node (ref "D28") (pin "1") (pinfunction "I/O1_1") (pintype "bidirectional"))
      (node (ref "IC9") (pin "110") (pinfunction "PA15_110") (pintype "passive"))
      (node (ref "J8") (pin "8") (pinfunction "8_8") (pintype "bidirectional"))
      (node (ref "R33") (pin "2") (pinfunction "2_2") (pintype "passive"))
    )
    (net (code "100") (name "/TDO") (class "Default")
      (node (ref "D28") (pin "6") (pinfunction "I/O4_6") (pintype "bidirectional"))
      (node (ref "IC9") (pin "133") (pinfunction "PB3_133") (pintype "passive"))
      (node (ref "J8") (pin "6") (pinfunction "6_6") (pintype "bidirectional"))
      (node (ref "R31") (pin "2") (pinfunction "2_2") (pintype "passive"))
    )
    (net (code "101") (name "/TERM_STAT0") (class "Default")
      (node (ref "IC9") (pin "80") (pinfunction "PD11_80") (pintype "passive"))
    )
    (net (code "102") (name "/TERM_STAT1") (class "Default")
      (node (ref "IC9") (pin "90") (pinfunction "PG5_90") (pintype "passive"))
    )
    (net (code "103") (name "/TMS") (class "Default")
      (node (ref "D28") (pin "4") (pinfunction "I/O3_4") (pintype "bidirectional"))
      (node (ref "IC9") (pin "105") (pinfunction "PA13_105") (pintype "passive"))
      (node (ref "J8") (pin "2") (pinfunction "2_2") (pintype "bidirectional"))
      (node (ref "R16") (pin "2") (pinfunction "2_2") (pintype "passive"))
    )
    (net (code "104") (name "/USART3_RX") (class "Default")
      (node (ref "IC9") (pin "78") (pinfunction "PD9_78") (pintype "passive"))
    )
    (net (code "105") (name "/USART3_TX") (class "Default")
      (node (ref "IC9") (pin "77") (pinfunction "PD8_77") (pintype "passive"))
    )
    (net (code "106") (name "/USB_ID") (class "Default")
      (node (ref "IC9") (pin "102") (pinfunction "PA10_102") (pintype "passive"))
    )
    (net (code "107") (name "/USB_N") (class "Default")
      (node (ref "IC9") (pin "103") (pinfunction "PA11_103") (pintype "passive"))
    )
    (net (code "108") (name "/USB_P") (class "Default")
      (node (ref "IC9") (pin "104") (pinfunction "PA12_104") (pintype "passive"))
    )
    (net (code "109") (name "/VBUS_DET") (class "Default")
      (node (ref "IC9") (pin "101") (pinfunction "PA9_101") (pintype "passive"))
    )
    (net (code "110") (name "AVDD") (class "Default")
      (node (ref "C107") (pin "2") (pinfunction "2_2") (pintype "passive"))
      (node (ref "C15") (pin "1") (pinfunction "1_1") (pintype "passive"))
      (node (ref "IC9") (pin "33") (pinfunction "VDDA_33") (pintype "passive"))
      (node (ref "L15") (pin "2") (pinfunction "2_2") (pintype "passive"))
    )
    (net (code "111") (name "GND") (class "Default")
      (node (ref "C107") (pin "1") (pinfunction "1_1") (pintype "passive"))
      (node (ref "C136") (pin "2") (pinfunction "2_2") (pintype "passive"))
      (node (ref "C14") (pin "1") (pinfunction "1_1") (pintype "passive"))
      (node (ref "C15") (pin "2") (pinfunction "2_2") (pintype "passive"))
      (node (ref "C21") (pin "1") (pinfunction "1_1") (pintype "passive"))
      (node (ref "C23") (pin "1") (pinfunction "1_1") (pintype "passive"))
      (node (ref "C24") (pin "2") (pinfunction "2_2") (pintype "passive"))
      (node (ref "C25") (pin "2") (pinfunction "2_2") (pintype "passive"))
      (node (ref "C31") (pin "2") (pinfunction "2_2") (pintype "passive"))
      (node (ref "C35") (pin "2") (pinfunction "2_2") (pintype "passive"))
      (node (ref "C37") (pin "2") (pinfunction "2_2") (pintype "passive"))
      (node (ref "C38") (pin "2") (pinfunction "2_2") (pintype "passive"))
      (node (ref "C41") (pin "2") (pinfunction "2_2") (pintype "passive"))
      (node (ref "C43") (pin "2") (pinfunction "2_2") (pintype "passive"))
      (node (ref "C57") (pin "2") (pinfunction "2_2") (pintype "passive"))
      (node (ref "C67") (pin "2") (pinfunction "2_2") (pintype "passive"))
      (node (ref "C70") (pin "2") (pinfunction "2_2") (pintype "passive"))
      (node (ref "C71") (pin "2") (pinfunction "2_2") (pintype "passive"))
      (node (ref "C72") (pin "2") (pinfunction "2_2") (pintype "passive"))
      (node (ref "C73") (pin "2") (pinfunction "2_2") (pintype "passive"))
      (node (ref "C74") (pin "2") (pinfunction "2_2") (pintype "passive"))
      (node (ref "C78") (pin "1") (pinfunction "1_1") (pintype "passive"))
      (node (ref "D28") (pin "2") (pinfunction "GND_2") (pintype "power_in"))
      (node (ref "IC10") (pin "1") (pinfunction "Vss_1") (pintype "power_in"))
      (node (ref "IC9") (pin "107") (pinfunction "VSS_2_107") (pintype "passive"))
      (node (ref "IC9") (pin "120") (pinfunction "VSS_10_120") (pintype "passive"))
      (node (ref "IC9") (pin "130") (pinfunction "VSS_11_130") (pintype "passive"))
      (node (ref "IC9") (pin "16") (pinfunction "VSS_5_16") (pintype "passive"))
      (node (ref "IC9") (pin "31") (pinfunction "VSSA/VREF-_31") (pintype "passive"))
      (node (ref "IC9") (pin "38") (pinfunction "VSS_4_38") (pintype "passive"))
      (node (ref "IC9") (pin "51") (pinfunction "VSS_6_51") (pintype "passive"))
      (node (ref "IC9") (pin "61") (pinfunction "VSS_7_61") (pintype "passive"))
      (node (ref "IC9") (pin "83") (pinfunction "VSS_8_83") (pintype "passive"))
      (node (ref "IC9") (pin "94") (pinfunction "VSS_9_94") (pintype "passive"))
      (node (ref "J8") (pin "3") (pinfunction "3_3") (pintype "bidirectional"))
      (node (ref "J8") (pin "5") (pinfunction "5_5") (pintype "bidirectional"))
      (node (ref "J8") (pin "9") (pinfunction "9_9") (pintype "bidirectional"))
      (node (ref "R182") (pin "2") (pinfunction "2_2") (pintype "passive"))
      (node (ref "R183") (pin "2") (pinfunction "2_2") (pintype "passive"))
      (node (ref "R30") (pin "1") (pinfunction "1_1") (pintype "passive"))
      (node (ref "R96") (pin "2") (pinfunction "2_2") (pintype "passive"))
    )
    (net (code "112") (name "Net-(C136-Pad1)") (class "Default")
      (node (ref "C136") (pin "1") (pinfunction "1_1") (pintype "passive"))
      (node (ref "R207") (pin "1") (pinfunction "1_1") (pintype "passive"))
    )
    (net (code "113") (name "Net-(D1-C)") (class "Default")
      (node (ref "D1") (pin "1") (pinfunction "C_1") (pintype "passive"))
      (node (ref "IC10") (pin "2") (pinfunction "~{RST}_2") (pintype "output"))
    )
    (net (code "114") (name "Net-(IC9A-PA3)") (class "Default")
      (node (ref "IC9") (pin "37") (pinfunction "PA3_37") (pintype "passive"))
      (node (ref "R176") (pin "1") (pinfunction "1_1") (pintype "passive"))
    )
    (net (code "115") (name "Net-(IC9A-PA6)") (class "Default")
      (node (ref "IC9") (pin "42") (pinfunction "PA6_42") (pintype "passive"))
      (node (ref "R136") (pin "1") (pinfunction "1_1") (pintype "passive"))
    )
    (net (code "116") (name "Net-(IC9A-PA8)") (class "Default")
      (node (ref "IC9") (pin "100") (pinfunction "PA8_100") (pintype "passive"))
      (node (ref "R177") (pin "2") (pinfunction "2_2") (pintype "passive"))
    )
    (net (code "117") (name "Net-(IC9A-PB2)") (class "Default")
      (node (ref "IC9") (pin "48") (pinfunction "PB2_48") (pintype "passive"))
      (node (ref "R12") (pin "2") (pinfunction "2_2") (pintype "passive"))
    )
    (net (code "118") (name "Net-(IC9A-PC11)") (class "Default")
      (node (ref "IC9") (pin "112") (pinfunction "PC11_112") (pintype "passive"))
      (node (ref "R185") (pin "2") (pinfunction "2_2") (pintype "passive"))
    )
    (net (code "119") (name "Net-(IC9B-PD1)") (class "Default")
      (node (ref "IC9") (pin "115") (pinfunction "PD1_115") (pintype "passive"))
      (node (ref "R178") (pin "2") (pinfunction "2_2") (pintype "passive"))
    )
    (net (code "120") (name "Net-(IC9B-PD7)") (class "Default")
      (node (ref "IC9") (pin "123") (pinfunction "PD7_123") (pintype "passive"))
      (node (ref "R128") (pin "1") (pinfunction "1_1") (pintype "passive"))
    )
    (net (code "121") (name "Net-(IC9B-PE7)") (class "Default")
      (node (ref "IC9") (pin "58") (pinfunction "PE7_58") (pintype "passive"))
      (node (ref "R186") (pin "1") (pinfunction "1_1") (pintype "passive"))
    )
    (net (code "122") (name "Net-(IC9B-PE8)") (class "Default")
      (node (ref "IC9") (pin "59") (pinfunction "PE8_59") (pintype "passive"))
      (node (ref "R187") (pin "1") (pinfunction "1_1") (pintype "passive"))
    )
    (net (code "123") (name "Net-(IC9B-PE9)") (class "Default")
      (node (ref "IC9") (pin "60") (pinfunction "PE9_60") (pintype "passive"))
      (node (ref "R188") (pin "1") (pinfunction "1_1") (pintype "passive"))
    )
    (net (code "124") (name "Net-(IC9B-PE10)") (class "Default")
      (node (ref "IC9") (pin "63") (pinfunction "PE10_63") (pintype "passive"))
      (node (ref "R189") (pin "1") (pinfunction "1_1") (pintype "passive"))
    )
    (net (code "125") (name "Net-(IC9B-PG10)") (class "Default")
      (node (ref "IC9") (pin "125") (pinfunction "PG10_125") (pintype "passive"))
      (node (ref "R131") (pin "2") (pinfunction "2_2") (pintype "passive"))
    )
    (net (code "126") (name "Net-(IC9B-PG11)") (class "Default")
      (node (ref "IC9") (pin "126") (pinfunction "PG11_126") (pintype "passive"))
      (node (ref "R132") (pin "2") (pinfunction "2_2") (pintype "passive"))
    )
    (net (code "127") (name "Net-(IC9C-BOOT0)") (class "Default")
      (node (ref "IC9") (pin "138") (pinfunction "BOOT0_138") (pintype "passive"))
      (node (ref "JP2") (pin "2") (pinfunction "E2_2") (pintype "passive"))
      (node (ref "R96") (pin "1") (pinfunction "1_1") (pintype "passive"))
    )
    (net (code "128") (name "Net-(IC9C-PDR_ON)") (class "Default")
      (node (ref "IC9") (pin "143") (pinfunction "PDR_ON_143") (pintype "passive"))
      (node (ref "R97") (pin "1") (pinfunction "1_1") (pintype "passive"))
    )
    (net (code "129") (name "Net-(IC9C-PH0{slash}OSC_IN)") (class "Default")
      (node (ref "C21") (pin "2") (pinfunction "2_2") (pintype "passive"))
      (node (ref "IC9") (pin "23") (pinfunction "PH0/OSC_IN_23") (pintype "passive"))
      (node (ref "Q1") (pin "2") (pinfunction "OSC2_2") (pintype "passive"))
      (node (ref "R179") (pin "2") (pinfunction "2_2") (pintype "passive"))
    )
    (net (code "130") (name "Net-(IC9C-PH1{slash}OSC_OUT)") (class "Default")
      (node (ref "C23") (pin "2") (pinfunction "2_2") (pintype "passive"))
      (node (ref "IC9") (pin "24") (pinfunction "PH1/OSC_OUT_24") (pintype "passive"))
      (node (ref "Q1") (pin "1") (pinfunction "OSC1_1") (pintype "passive"))
    )
    (net (code "131") (name "Net-(IC9C-VCAP1)") (class "Default")
      (node (ref "C25") (pin "1") (pinfunction "1_1") (pintype "passive"))
      (node (ref "IC9") (pin "71") (pinfunction "VCAP1_71") (pintype "passive"))
    )
    (net (code "132") (name "Net-(IC9C-VCAP2)") (class "Default")
      (node (ref "C24") (pin "1") (pinfunction "1_1") (pintype "passive"))
      (node (ref "IC9") (pin "106") (pinfunction "VCAP2_106") (pintype "passive"))
    )
    (net (code "133") (name "Net-(IC9C-VREF+)") (class "Default")
      (node (ref "C14") (pin "2") (pinfunction "2_2") (pintype "passive"))
      (node (ref "C31") (pin "1") (pinfunction "1_1") (pintype "passive"))
      (node (ref "IC9") (pin "32") (pinfunction "VREF+_32") (pintype "passive"))
      (node (ref "R95") (pin "2") (pinfunction "2_2") (pintype "passive"))
    )
    (net (code "134") (name "P3V3") (class "Default")
      (node (ref "C35") (pin "1") (pinfunction "1_1") (pintype "passive"))
      (node (ref "C37") (pin "1") (pinfunction "1_1") (pintype "passive"))
      (node (ref "C38") (pin "1") (pinfunction "1_1") (pintype "passive"))
      (node (ref "C41") (pin "1") (pinfunction "1_1") (pintype "passive"))
      (node (ref "C43") (pin "1") (pinfunction "1_1") (pintype "passive"))
      (node (ref "C57") (pin "1") (pinfunction "1_1") (pintype "passive"))
      (node (ref "C67") (pin "1") (pinfunction "1_1") (pintype "passive"))
      (node (ref "C70") (pin "1") (pinfunction "1_1") (pintype "passive"))
      (node (ref "C71") (pin "1") (pinfunction "1_1") (pintype "passive"))
      (node (ref "C72") (pin "1") (pinfunction "1_1") (pintype "passive"))
      (node (ref "C73") (pin "1") (pinfunction "1_1") (pintype "passive"))
      (node (ref "C74") (pin "1") (pinfunction "1_1") (pintype "passive"))
      (node (ref "C78") (pin "2") (pinfunction "2_2") (pintype "passive"))
      (node (ref "D28") (pin "5") (pinfunction "VBUS_5") (pintype "power_in"))
      (node (ref "IC10") (pin "3") (pinfunction "Vcc_3") (pintype "power_in"))
      (node (ref "IC9") (pin "108") (pinfunction "VDD_2_108") (pintype "passive"))
      (node (ref "IC9") (pin "121") (pinfunction "VDD_10_121") (pintype "passive"))
      (node (ref "IC9") (pin "131") (pinfunction "VDD_11_131") (pintype "passive"))
      (node (ref "IC9") (pin "144") (pinfunction "VDD_3_144") (pintype "passive"))
      (node (ref "IC9") (pin "17") (pinfunction "VDD_5_17") (pintype "passive"))
      (node (ref "IC9") (pin "30") (pinfunction "VDD_12_30") (pintype "passive"))
      (node (ref "IC9") (pin "39") (pinfunction "VDD_4_39") (pintype "passive"))
      (node (ref "IC9") (pin "52") (pinfunction "VDD_6_52") (pintype "passive"))
      (node (ref "IC9") (pin "6") (pinfunction "VBAT_6") (pintype "passive"))
      (node (ref "IC9") (pin "62") (pinfunction "VDD_7_62") (pintype "passive"))
      (node (ref "IC9") (pin "72") (pinfunction "VDD_1_72") (pintype "passive"))
      (node (ref "IC9") (pin "84") (pinfunction "VDD_8_84") (pintype "passive"))
      (node (ref "IC9") (pin "95") (pinfunction "VDD33_USB_95") (pintype "passive"))
      (node (ref "J8") (pin "1") (pinfunction "1_1") (pintype "bidirectional"))
      (node (ref "JP2") (pin "1") (pinfunction "E1_1") (pintype "passive"))
      (node (ref "L15") (pin "1") (pinfunction "1_1") (pintype "passive"))
      (node (ref "R13") (pin "1") (pinfunction "1_1") (pintype "passive"))
      (node (ref "R16") (pin "1") (pinfunction "1_1") (pintype "passive"))
      (node (ref "R180") (pin "2") (pinfunction "2_2") (pintype "passive"))
      (node (ref "R181") (pin "2") (pinfunction "2_2") (pintype "passive"))
      (node (ref "R31") (pin "1") (pinfunction "1_1") (pintype "passive"))
      (node (ref "R33") (pin "1") (pinfunction "1_1") (pintype "passive"))
      (node (ref "R97") (pin "2") (pinfunction "2_2") (pintype "passive"))
    )
    (net (code "135") (name "unconnected-(IC9A-PC0-Pad26)") (class "Default")
      (node (ref "IC9") (pin "26") (pinfunction "PC0_26") (pintype "passive"))
    )
    (net (code "136") (name "unconnected-(IC9A-PC8-Pad98)") (class "Default")
      (node (ref "IC9") (pin "98") (pinfunction "PC8_98") (pintype "passive"))
    )
    (net (code "137") (name "unconnected-(IC9A-PC13-Pad7)") (class "Default")
      (node (ref "IC9") (pin "7") (pinfunction "PC13_7") (pintype "passive"))
    )
    (net (code "138") (name "unconnected-(IC9B-PD0-Pad114)") (class "Default")
      (node (ref "IC9") (pin "114") (pinfunction "PD0_114") (pintype "passive"))
    )
    (net (code "139") (name "unconnected-(IC9B-PF15-Pad55)") (class "Default")
      (node (ref "IC9") (pin "55") (pinfunction "PF15_55") (pintype "passive"))
    )
    (net (code "140") (name "unconnected-(IC9B-PG15-Pad132)") (class "Default")
      (node (ref "IC9") (pin "132") (pinfunction "PG15_132") (pintype "passive"))
    )
    (net (code "141") (name "unconnected-(J8-Pad7)") (class "Default")
      (node (ref "J8") (pin "7") (pinfunction "7_7") (pintype "bidirectional"))
    )
  )
)
